# ee242a-lab4-amp.net
KiCad netlist of a schematic drawn in EAGLE
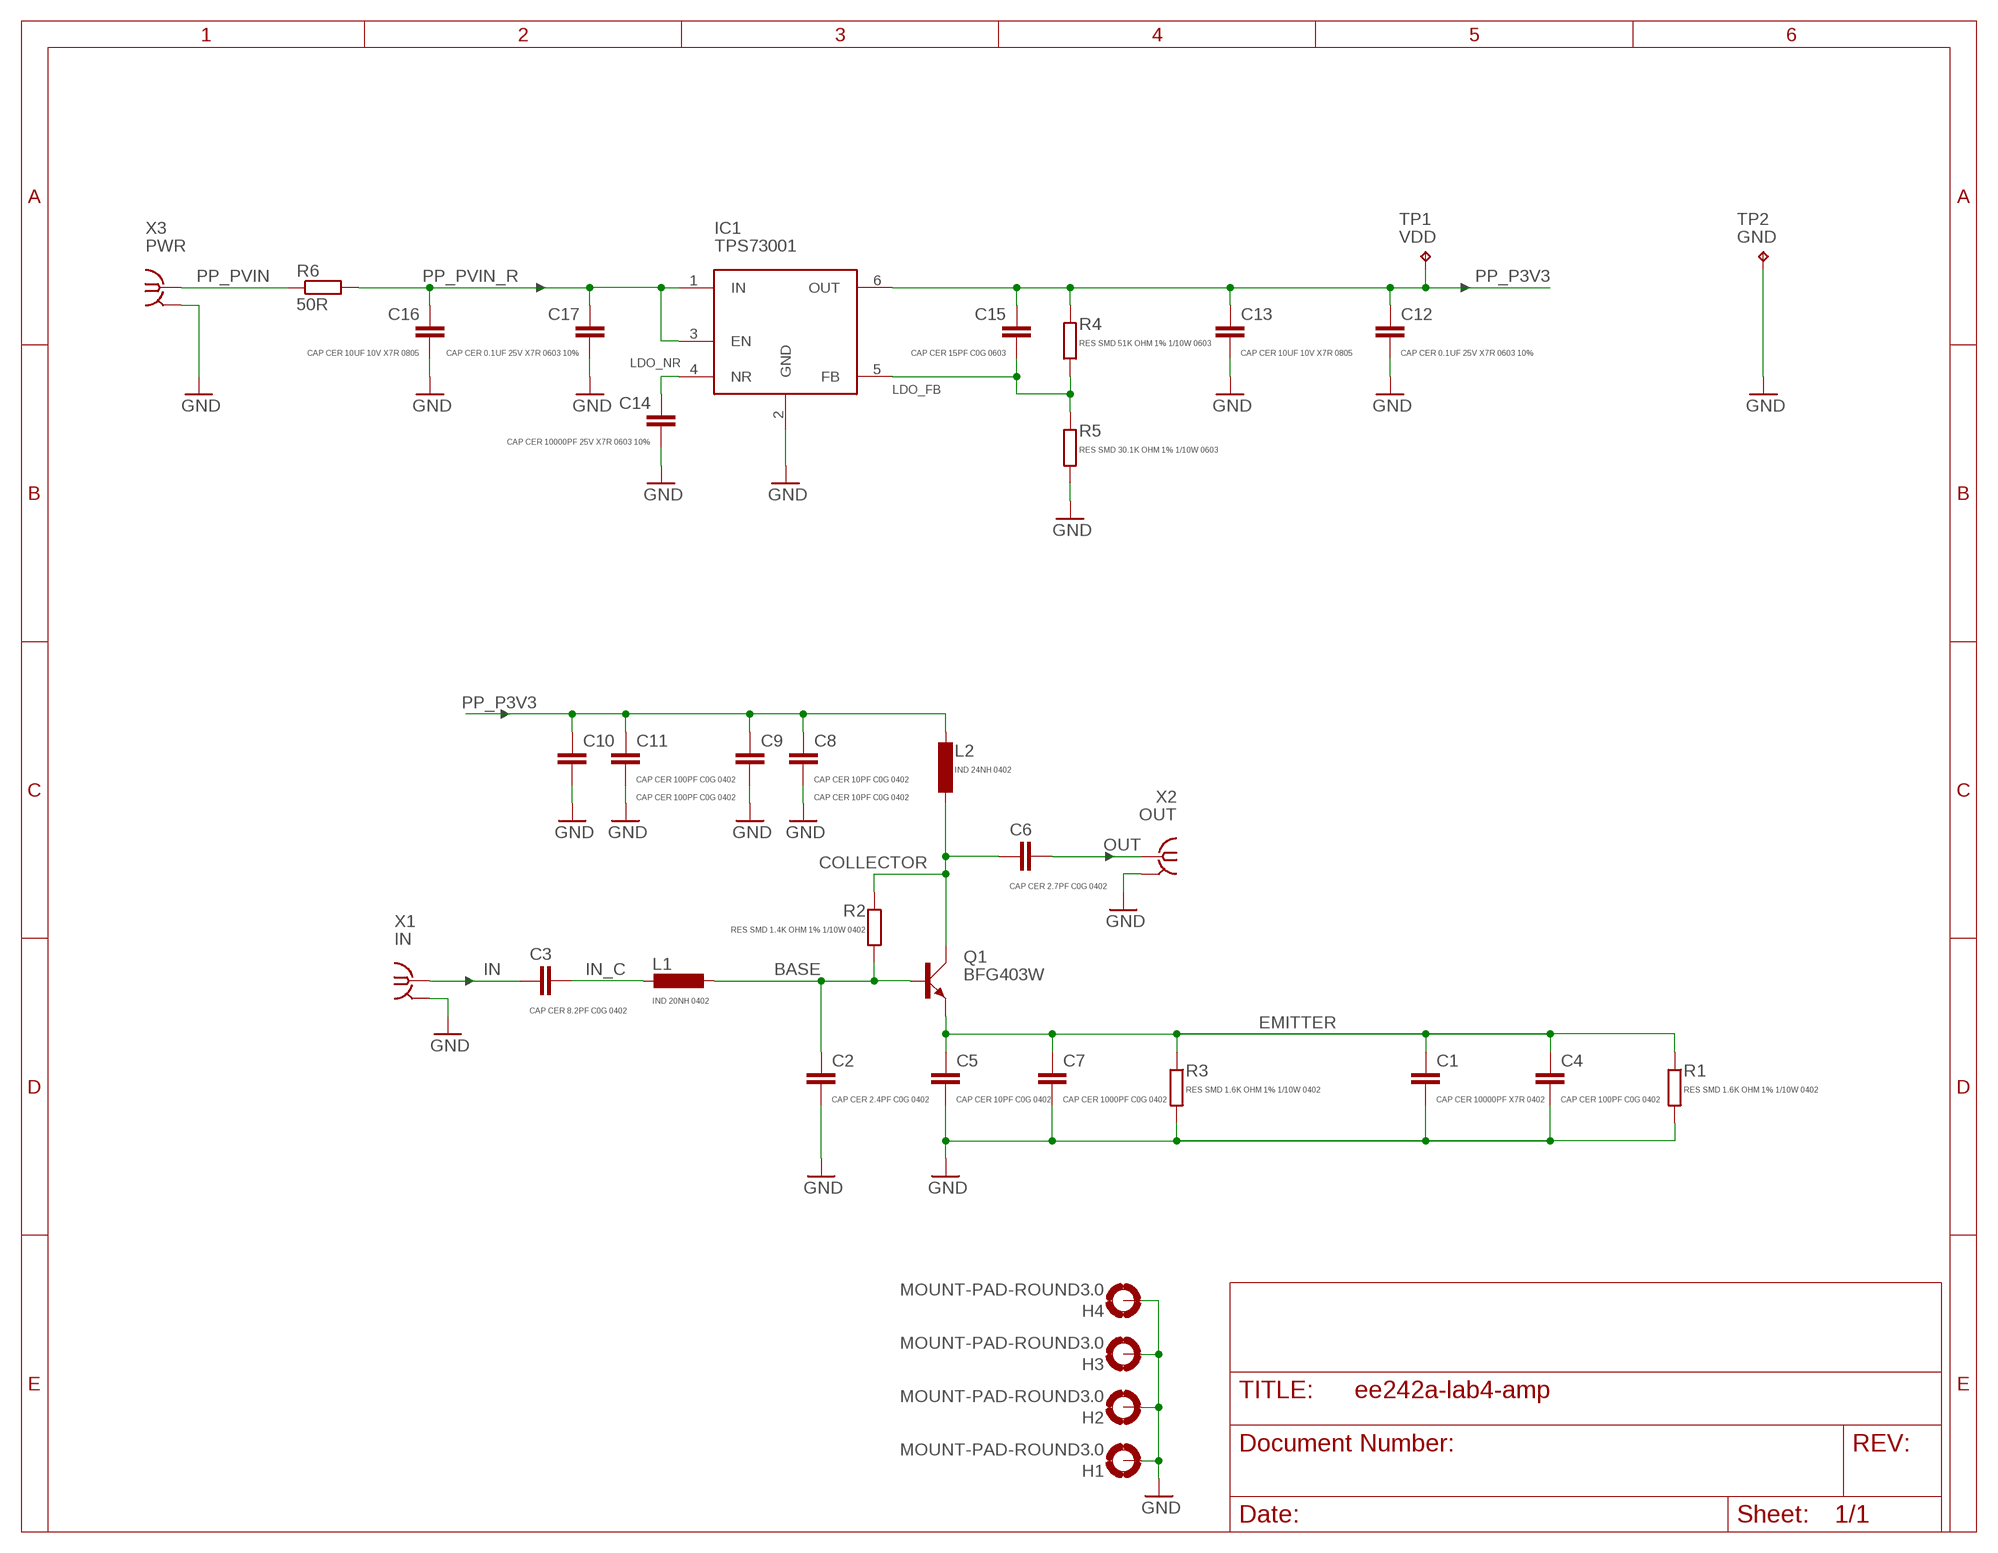
[diagram p0: schematic, sheet 1]

(export (version "E")
  (design (tool "Eeschema 10.0.6"))
  (components
    (comp (ref "C1")
      (value "CAP CER 10000PF X7R 0402")
      (footprint "eagle-import:C0402")
      (libsource (lib "eagle-import") (part "rcl-modified-footprints_C-EUC0402"))
    )
    (comp (ref "C2")
      (value "CAP CER 2.4PF C0G 0402")
      (footprint "eagle-import:C0402")
      (libsource (lib "eagle-import") (part "rcl-modified-footprints_C-EUC0402"))
    )
    (comp (ref "C3")
      (value "CAP CER 8.2PF C0G 0402")
      (footprint "eagle-import:C0402")
      (libsource (lib "eagle-import") (part "rcl-modified-footprints_C-EUC0402"))
    )
    (comp (ref "C4")
      (value "CAP CER 100PF C0G 0402")
      (footprint "eagle-import:C0402")
      (libsource (lib "eagle-import") (part "rcl-modified-footprints_C-EUC0402"))
    )
    (comp (ref "C5")
      (value "CAP CER 10PF C0G 0402")
      (footprint "eagle-import:C0402")
      (libsource (lib "eagle-import") (part "rcl-modified-footprints_C-EUC0402"))
    )
    (comp (ref "C6")
      (value "CAP CER 2.7PF C0G 0402")
      (footprint "eagle-import:C0402")
      (libsource (lib "eagle-import") (part "rcl-modified-footprints_C-EUC0402"))
    )
    (comp (ref "C7")
      (value "CAP CER 1000PF C0G 0402")
      (footprint "eagle-import:C0402")
      (libsource (lib "eagle-import") (part "rcl-modified-footprints_C-EUC0402"))
    )
    (comp (ref "C8")
      (value "CAP CER 10PF C0G 0402")
      (footprint "eagle-import:C0402")
      (libsource (lib "eagle-import") (part "rcl-modified-footprints_C-EUC0402"))
    )
    (comp (ref "C9")
      (value "CAP CER 10PF C0G 0402")
      (footprint "eagle-import:C0402")
      (libsource (lib "eagle-import") (part "rcl-modified-footprints_C-EUC0402"))
    )
    (comp (ref "C10")
      (value "CAP CER 100PF C0G 0402")
      (footprint "eagle-import:C0402")
      (libsource (lib "eagle-import") (part "rcl-modified-footprints_C-EUC0402"))
    )
    (comp (ref "C11")
      (value "CAP CER 100PF C0G 0402")
      (footprint "eagle-import:C0402")
      (libsource (lib "eagle-import") (part "rcl-modified-footprints_C-EUC0402"))
    )
    (comp (ref "C12")
      (value "CAP CER 0.1UF 25V X7R 0603 10%")
      (footprint "eagle-import:C0603")
      (libsource (lib "eagle-import") (part "rcl-modified-footprints_C-EUC0603"))
    )
    (comp (ref "C13")
      (value "CAP CER 10UF 10V X7R 0805")
      (footprint "eagle-import:C0805")
      (libsource (lib "eagle-import") (part "C-EUC0805"))
    )
    (comp (ref "C14")
      (value "CAP CER 10000PF 25V X7R 0603 10%")
      (footprint "eagle-import:C0603")
      (libsource (lib "eagle-import") (part "rcl-modified-footprints_C-EUC0603"))
    )
    (comp (ref "C15")
      (value "CAP CER 15PF C0G 0603")
      (footprint "eagle-import:C0603")
      (libsource (lib "eagle-import") (part "rcl-modified-footprints_C-EUC0603"))
    )
    (comp (ref "C16")
      (value "CAP CER 10UF 10V X7R 0805")
      (footprint "eagle-import:C0805")
      (libsource (lib "eagle-import") (part "C-EUC0805"))
    )
    (comp (ref "C17")
      (value "CAP CER 0.1UF 25V X7R 0603 10%")
      (footprint "eagle-import:C0603")
      (libsource (lib "eagle-import") (part "rcl-modified-footprints_C-EUC0603"))
    )
    (comp (ref "H1")
      (value "MOUNT-PAD-ROUND3.0")
      (footprint "eagle-import:3,0-PAD")
      (libsource (lib "eagle-import") (part "MOUNT-PAD-ROUND3.0"))
    )
    (comp (ref "H2")
      (value "MOUNT-PAD-ROUND3.0")
      (footprint "eagle-import:3,0-PAD")
      (libsource (lib "eagle-import") (part "MOUNT-PAD-ROUND3.0"))
    )
    (comp (ref "H3")
      (value "MOUNT-PAD-ROUND3.0")
      (footprint "eagle-import:3,0-PAD")
      (libsource (lib "eagle-import") (part "MOUNT-PAD-ROUND3.0"))
    )
    (comp (ref "H4")
      (value "MOUNT-PAD-ROUND3.0")
      (footprint "eagle-import:3,0-PAD")
      (libsource (lib "eagle-import") (part "MOUNT-PAD-ROUND3.0"))
    )
    (comp (ref "IC1")
      (value "TPS73001")
      (footprint "eagle-import:SOT23-6L")
      (libsource (lib "eagle-import") (part "TPS73001"))
    )
    (comp (ref "L1")
      (value "IND 20NH 0402")
      (footprint "eagle-import:R0402")
      (libsource (lib "eagle-import") (part "L-EU0402"))
    )
    (comp (ref "L2")
      (value "IND 24NH 0402")
      (footprint "eagle-import:R0402")
      (libsource (lib "eagle-import") (part "L-EU0402"))
    )
    (comp (ref "Q1")
      (value "BFG403W")
      (footprint "eagle-import:SOT343R")
      (libsource (lib "eagle-import") (part "BFG403W"))
    )
    (comp (ref "R1")
      (value "RES SMD 1.6K OHM 1% 1/10W 0402")
      (footprint "eagle-import:R0402")
      (libsource (lib "eagle-import") (part "R-EU_R0402"))
    )
    (comp (ref "R2")
      (value "RES SMD 1.4K OHM 1% 1/10W 0402")
      (footprint "eagle-import:R0402")
      (libsource (lib "eagle-import") (part "R-EU_R0402"))
    )
    (comp (ref "R3")
      (value "RES SMD 1.6K OHM 1% 1/10W 0402")
      (footprint "eagle-import:R0402")
      (libsource (lib "eagle-import") (part "R-EU_R0402"))
    )
    (comp (ref "R4")
      (value "RES SMD 51K OHM 1% 1/10W 0603")
      (footprint "eagle-import:R0603")
      (libsource (lib "eagle-import") (part "R-EU_R0603"))
    )
    (comp (ref "R5")
      (value "RES SMD 30.1K OHM 1% 1/10W 0603")
      (footprint "eagle-import:R0603")
      (libsource (lib "eagle-import") (part "R-EU_R0603"))
    )
    (comp (ref "R6")
      (value "50R")
      (footprint "eagle-import:R0805")
      (libsource (lib "eagle-import") (part "R-EU_R0805"))
    )
    (comp (ref "TP1")
      (value "VDD")
      (footprint "eagle-import:KEYSTONE_5000_MINIATURE")
      (libsource (lib "eagle-import") (part "KEYSTONE_5000"))
    )
    (comp (ref "TP2")
      (value "GND")
      (footprint "eagle-import:KEYSTONE_5000_MINIATURE")
      (libsource (lib "eagle-import") (part "KEYSTONE_5000"))
    )
    (comp (ref "X1")
      (value "IN")
      (footprint "eagle-import:J502-ND-142-0701-881_886")
      (fields (field (name "MF") "JOHNSON COMPONENTS") (field (name "MPN") "142-0701-881"))
      (libsource (lib "eagle-import") (part "SMA-142-0701-881/886"))
    )
    (comp (ref "X2")
      (value "OUT")
      (footprint "eagle-import:J502-ND-142-0701-881_886")
      (fields (field (name "MF") "JOHNSON COMPONENTS") (field (name "MPN") "142-0701-881"))
      (libsource (lib "eagle-import") (part "SMA-142-0701-881/886"))
    )
    (comp (ref "X3")
      (value "PWR")
      (footprint "eagle-import:J502-ND-142-0701-881_886")
      (fields (field (name "MF") "JOHNSON COMPONENTS") (field (name "MPN") "142-0701-881"))
      (libsource (lib "eagle-import") (part "SMA-142-0701-881/886"))
    )
  )
  (nets
    (net (code "1") (name "/BASE") (class "Default")
      (node (ref "C2") (pin "1") (pinfunction "1_1") (pintype "passive"))
      (node (ref "L1") (pin "2") (pinfunction "2_2") (pintype "passive"))
      (node (ref "Q1") (pin "2") (pinfunction "B_2") (pintype "passive"))
      (node (ref "R2") (pin "2") (pinfunction "2_2") (pintype "passive"))
    )
    (net (code "2") (name "/COLLECTOR") (class "Default")
      (node (ref "C6") (pin "1") (pinfunction "1_1") (pintype "passive"))
      (node (ref "L2") (pin "2") (pinfunction "2_2") (pintype "passive"))
      (node (ref "Q1") (pin "4") (pinfunction "C_4") (pintype "passive"))
      (node (ref "R2") (pin "1") (pinfunction "1_1") (pintype "passive"))
    )
    (net (code "3") (name "/EMITTER") (class "Default")
      (node (ref "C1") (pin "1") (pinfunction "1_1") (pintype "passive"))
      (node (ref "C4") (pin "1") (pinfunction "1_1") (pintype "passive"))
      (node (ref "C5") (pin "1") (pinfunction "1_1") (pintype "passive"))
      (node (ref "C7") (pin "1") (pinfunction "1_1") (pintype "passive"))
      (node (ref "Q1") (pin "1") (pinfunction "E_1") (pintype "passive"))
      (node (ref "Q1") (pin "3") (pinfunction "E_3") (pintype "passive"))
      (node (ref "R1") (pin "1") (pinfunction "1_1") (pintype "passive"))
      (node (ref "R3") (pin "1") (pinfunction "1_1") (pintype "passive"))
    )
    (net (code "4") (name "/IN") (class "Default")
      (node (ref "C3") (pin "1") (pinfunction "1_1") (pintype "passive"))
      (node (ref "X1") (pin "1") (pinfunction "1_1") (pintype "passive"))
    )
    (net (code "5") (name "/IN_C") (class "Default")
      (node (ref "C3") (pin "2") (pinfunction "2_2") (pintype "passive"))
      (node (ref "L1") (pin "1") (pinfunction "1_1") (pintype "passive"))
    )
    (net (code "6") (name "/LDO_FB") (class "Default")
      (node (ref "C15") (pin "2") (pinfunction "2_2") (pintype "passive"))
      (node (ref "IC1") (pin "5") (pinfunction "FB_5") (pintype "bidirectional"))
      (node (ref "R4") (pin "1") (pinfunction "1_1") (pintype "passive"))
      (node (ref "R5") (pin "1") (pinfunction "1_1") (pintype "passive"))
    )
    (net (code "7") (name "/LDO_NR") (class "Default")
      (node (ref "C14") (pin "1") (pinfunction "1_1") (pintype "passive"))
      (node (ref "IC1") (pin "4") (pinfunction "NR_4") (pintype "bidirectional"))
    )
    (net (code "8") (name "/OUT") (class "Default")
      (node (ref "C6") (pin "2") (pinfunction "2_2") (pintype "passive"))
      (node (ref "X2") (pin "1") (pinfunction "1_1") (pintype "passive"))
    )
    (net (code "9") (name "/PP_P3V3") (class "Default")
      (node (ref "C10") (pin "1") (pinfunction "1_1") (pintype "passive"))
      (node (ref "C11") (pin "1") (pinfunction "1_1") (pintype "passive"))
      (node (ref "C12") (pin "1") (pinfunction "1_1") (pintype "passive"))
      (node (ref "C13") (pin "1") (pinfunction "1_1") (pintype "passive"))
      (node (ref "C15") (pin "1") (pinfunction "1_1") (pintype "passive"))
      (node (ref "C8") (pin "1") (pinfunction "1_1") (pintype "passive"))
      (node (ref "C9") (pin "1") (pinfunction "1_1") (pintype "passive"))
      (node (ref "IC1") (pin "6") (pinfunction "OUT_6") (pintype "bidirectional"))
      (node (ref "L2") (pin "1") (pinfunction "1_1") (pintype "passive"))
      (node (ref "R4") (pin "2") (pinfunction "2_2") (pintype "passive"))
      (node (ref "TP1") (pin "P$1") (pinfunction "P$1_P$1") (pintype "bidirectional"))
    )
    (net (code "10") (name "/PP_PVIN") (class "Default")
      (node (ref "R6") (pin "1") (pinfunction "1_1") (pintype "passive"))
      (node (ref "X3") (pin "1") (pinfunction "1_1") (pintype "passive"))
    )
    (net (code "11") (name "/PP_PVIN_R") (class "Default")
      (node (ref "C16") (pin "1") (pinfunction "1_1") (pintype "passive"))
      (node (ref "C17") (pin "1") (pinfunction "1_1") (pintype "passive"))
      (node (ref "IC1") (pin "1") (pinfunction "IN_1") (pintype "bidirectional"))
      (node (ref "IC1") (pin "3") (pinfunction "EN_3") (pintype "bidirectional"))
      (node (ref "R6") (pin "2") (pinfunction "2_2") (pintype "passive"))
    )
    (net (code "12") (name "GND") (class "Default")
      (node (ref "C1") (pin "2") (pinfunction "2_2") (pintype "passive"))
      (node (ref "C10") (pin "2") (pinfunction "2_2") (pintype "passive"))
      (node (ref "C11") (pin "2") (pinfunction "2_2") (pintype "passive"))
      (node (ref "C12") (pin "2") (pinfunction "2_2") (pintype "passive"))
      (node (ref "C13") (pin "2") (pinfunction "2_2") (pintype "passive"))
      (node (ref "C14") (pin "2") (pinfunction "2_2") (pintype "passive"))
      (node (ref "C16") (pin "2") (pinfunction "2_2") (pintype "passive"))
      (node (ref "C17") (pin "2") (pinfunction "2_2") (pintype "passive"))
      (node (ref "C2") (pin "2") (pinfunction "2_2") (pintype "passive"))
      (node (ref "C4") (pin "2") (pinfunction "2_2") (pintype "passive"))
      (node (ref "C5") (pin "2") (pinfunction "2_2") (pintype "passive"))
      (node (ref "C7") (pin "2") (pinfunction "2_2") (pintype "passive"))
      (node (ref "C8") (pin "2") (pinfunction "2_2") (pintype "passive"))
      (node (ref "C9") (pin "2") (pinfunction "2_2") (pintype "passive"))
      (node (ref "H1") (pin "B3,0") (pinfunction "MOUNT_B3,0") (pintype "passive"))
      (node (ref "H2") (pin "B3,0") (pinfunction "MOUNT_B3,0") (pintype "passive"))
      (node (ref "H3") (pin "B3,0") (pinfunction "MOUNT_B3,0") (pintype "passive"))
      (node (ref "H4") (pin "B3,0") (pinfunction "MOUNT_B3,0") (pintype "passive"))
      (node (ref "IC1") (pin "2") (pinfunction "GND_2") (pintype "bidirectional"))
      (node (ref "R1") (pin "2") (pinfunction "2_2") (pintype "passive"))
      (node (ref "R3") (pin "2") (pinfunction "2_2") (pintype "passive"))
      (node (ref "R5") (pin "2") (pinfunction "2_2") (pintype "passive"))
      (node (ref "TP2") (pin "P$1") (pinfunction "P$1_P$1") (pintype "bidirectional"))
      (node (ref "X1") (pin "G@1") (pinfunction "GND_G@1") (pintype "power_in"))
      (node (ref "X2") (pin "G@1") (pinfunction "GND_G@1") (pintype "power_in"))
      (node (ref "X3") (pin "G@1") (pinfunction "GND_G@1") (pintype "power_in"))
    )
  )
)
